# arduino_shield.net
KiCad netlist of a schematic drawn in Altium Designer
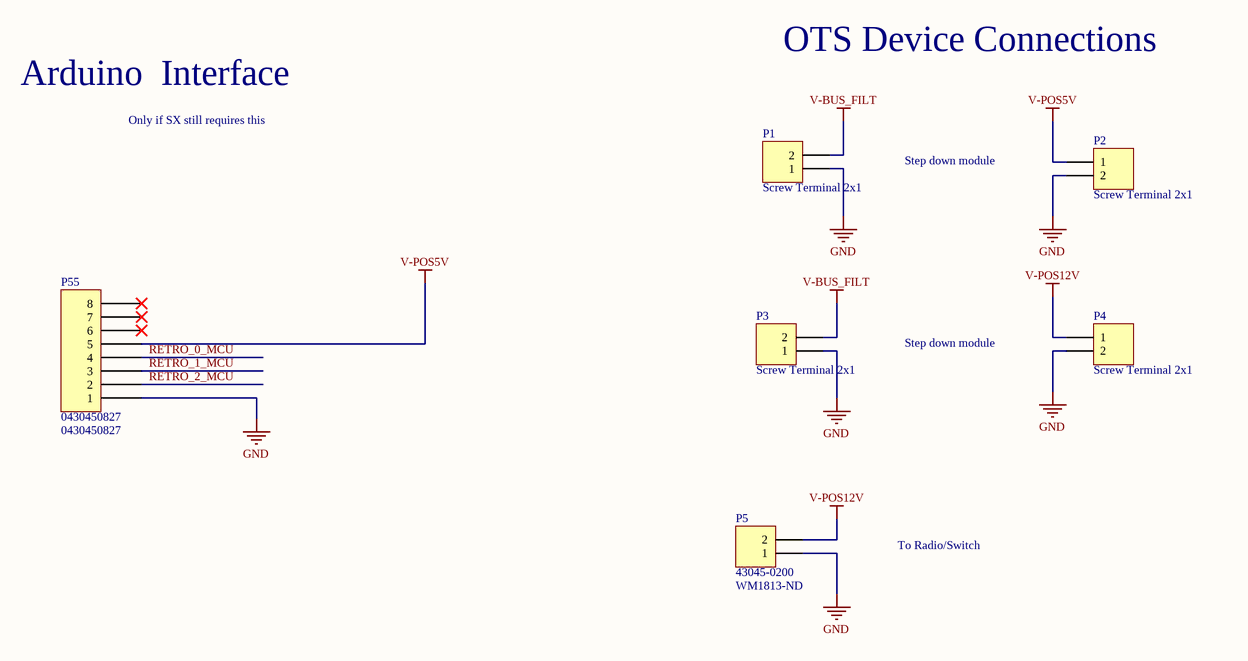
[diagram p0: arduino_shield.SchDoc]

(export (version "E")
  (design (tool "Eeschema 10.0.6"))
  (components
    (comp (ref "P1")
      (value "Screw Terminal 2x1")
      (footprint "2POS TERM BLOCK")
      (description "Screw Terminal, 2-Pin")
      (libsource (lib "") (part "Screw Terminal 2x1_1"))
    )
    (comp (ref "P2")
      (value "Screw Terminal 2x1")
      (footprint "2POS TERM BLOCK")
      (description "Screw Terminal, 2-Pin")
      (libsource (lib "connector") (part "Screw Terminal 2x1"))
    )
    (comp (ref "P3")
      (value "Screw Terminal 2x1")
      (footprint "2POS TERM BLOCK")
      (description "Screw Terminal, 2-Pin")
      (libsource (lib "") (part "Screw Terminal 2x1_1"))
    )
    (comp (ref "P4")
      (value "Screw Terminal 2x1")
      (footprint "2POS TERM BLOCK")
      (description "Screw Terminal, 2-Pin")
      (libsource (lib "connector") (part "Screw Terminal 2x1"))
    )
    (comp (ref "P5")
      (value "43045-0200")
      (footprint "430450200")
      (description "CONN HEADER R/A 2POS")
      (fields (field (name "MANUFACTURER") "Molex") (field (name "SUPPLIER PART NUMBER 1") "WM1813-ND"))
      (libsource (lib "connector") (part "43045-0200"))
    )
    (comp (ref "P55")
      (value "0430450827")
      (footprint "0430450827")
      (description "CONN HEADER VERT 8POS 3MM")
      (fields (field (name "MANUFACTURER") "Molex") (field (name "MANUFACTURER PART NUMBER") "0430450827"))
      (libsource (lib "connector") (part "0430450827"))
    )
  )
  (nets
    (net (code "1") (name "/RETRO_0_MCU") (class "Default")
      (node (ref "P55") (pin "4") (pinfunction "4_4") (pintype "passive"))
    )
    (net (code "2") (name "/RETRO_1_MCU") (class "Default")
      (node (ref "P55") (pin "3") (pinfunction "3_3") (pintype "passive"))
    )
    (net (code "3") (name "/RETRO_2_MCU") (class "Default")
      (node (ref "P55") (pin "2") (pinfunction "2_2") (pintype "passive"))
    )
    (net (code "4") (name "GND") (class "Default")
      (node (ref "P1") (pin "1") (pinfunction "1_1") (pintype "passive"))
      (node (ref "P2") (pin "2") (pinfunction "2_2") (pintype "passive"))
      (node (ref "P3") (pin "1") (pinfunction "1_1") (pintype "passive"))
      (node (ref "P4") (pin "2") (pinfunction "2_2") (pintype "passive"))
      (node (ref "P5") (pin "1") (pinfunction "1_1") (pintype "passive"))
      (node (ref "P55") (pin "1") (pinfunction "1_1") (pintype "passive"))
    )
    (net (code "5") (name "V-BUS_FILT") (class "Default")
      (node (ref "P1") (pin "2") (pinfunction "2_2") (pintype "passive"))
      (node (ref "P3") (pin "2") (pinfunction "2_2") (pintype "passive"))
    )
    (net (code "6") (name "V-POS5V") (class "Default")
      (node (ref "P2") (pin "1") (pinfunction "1_1") (pintype "passive"))
      (node (ref "P55") (pin "5") (pinfunction "5_5") (pintype "passive"))
    )
    (net (code "7") (name "V-POS12V") (class "Default")
      (node (ref "P4") (pin "1") (pinfunction "1_1") (pintype "passive"))
      (node (ref "P5") (pin "2") (pinfunction "2_2") (pintype "passive"))
    )
    (net (code "8") (name "unconnected-(P55-Pad6)") (class "Default")
      (node (ref "P55") (pin "6") (pinfunction "6_6") (pintype "passive+no_connect"))
    )
    (net (code "9") (name "unconnected-(P55-Pad7)") (class "Default")
      (node (ref "P55") (pin "7") (pinfunction "7_7") (pintype "passive+no_connect"))
    )
    (net (code "10") (name "unconnected-(P55-Pad8)") (class "Default")
      (node (ref "P55") (pin "8") (pinfunction "8_8") (pintype "passive+no_connect"))
    )
  )
)
